# latdr31.net
KiCad netlist of a schematic drawn in EAGLE
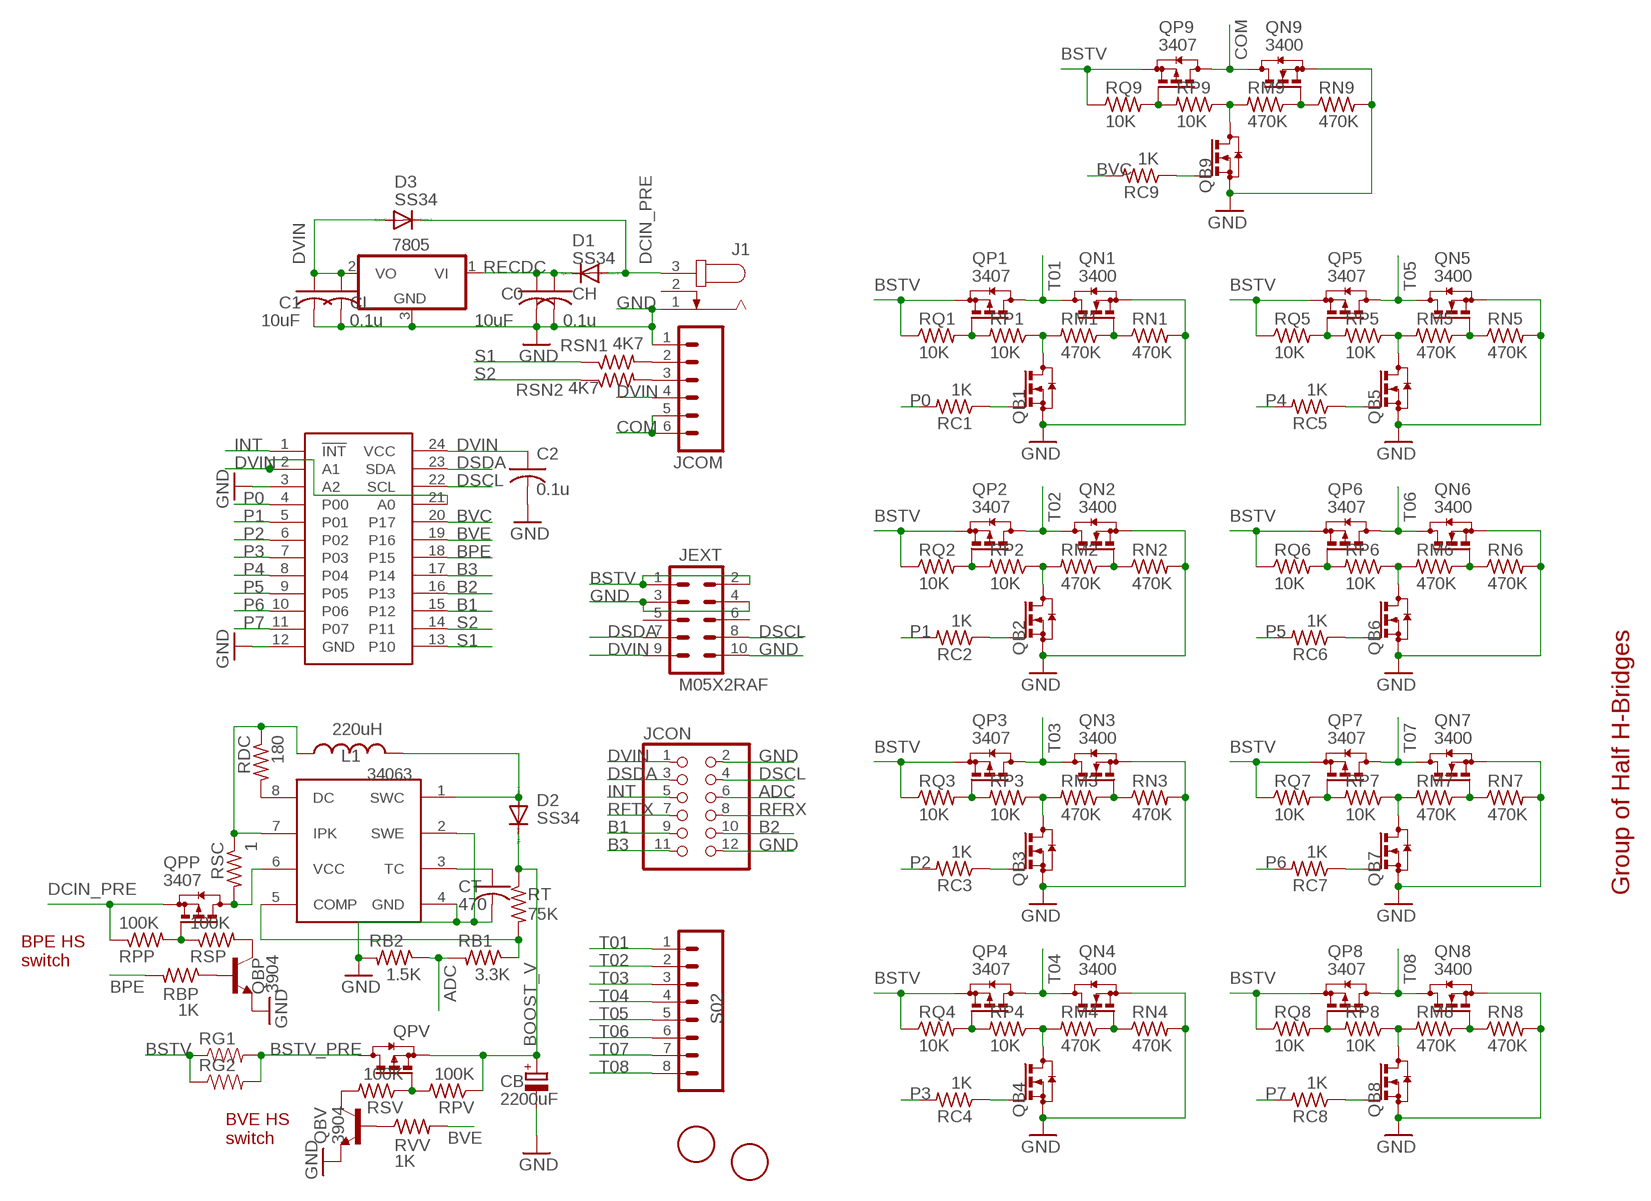
[diagram p0: schematic, sheet 1]

(export (version "E")
  (design (tool "Eeschema 10.0.6"))
  (components
    (comp (ref "0F")
      (value "FIDUCIAL")
      (footprint "eagle-import:FIDUCIAL_1MM")
      (libsource (lib "eagle-import") (part "FIDUCIAL"))
    )
    (comp (ref "1F")
      (value "FIDUCIAL")
      (footprint "eagle-import:FIDUCIAL_1MM")
      (libsource (lib "eagle-import") (part "FIDUCIAL"))
    )
    (comp (ref "7805")
      (value "7805DT")
      (footprint "eagle-import:TO252")
      (libsource (lib "eagle-import") (part "78DT05"))
    )
    (comp (ref "34063")
      (value "MC33063/MC34063D")
      (footprint "eagle-import:SO08")
      (libsource (lib "eagle-import") (part "MC33063/MC34063D"))
    )
    (comp (ref "C0")
      (value "10uF")
      (footprint "eagle-import:C0805K")
      (libsource (lib "eagle-import") (part "C-USC0805K"))
    )
    (comp (ref "C1")
      (value "10uF")
      (footprint "eagle-import:C0805K")
      (libsource (lib "eagle-import") (part "C-USC0805K"))
    )
    (comp (ref "C2")
      (value "0.1u")
      (footprint "eagle-import:C0603")
      (libsource (lib "eagle-import") (part "C-USC0603"))
    )
    (comp (ref "CB")
      (value "2200uF")
      (footprint "eagle-import:E7,5-16")
      (libsource (lib "eagle-import") (part "CPOL-EUE7.5-16"))
    )
    (comp (ref "CH")
      (value "0.1u")
      (footprint "eagle-import:C0603")
      (libsource (lib "eagle-import") (part "C-USC0603"))
    )
    (comp (ref "CL")
      (value "0.1u")
      (footprint "eagle-import:C0603")
      (libsource (lib "eagle-import") (part "C-USC0603"))
    )
    (comp (ref "CT")
      (value "470")
      (footprint "eagle-import:C0603K")
      (libsource (lib "eagle-import") (part "C-USC0603K"))
    )
    (comp (ref "D1")
      (value "SS34")
      (footprint "eagle-import:SMB")
      (libsource (lib "eagle-import") (part "DIODE-SMB"))
    )
    (comp (ref "D2")
      (value "SS34")
      (footprint "eagle-import:SMB")
      (libsource (lib "eagle-import") (part "DIODE-SMB"))
    )
    (comp (ref "D3")
      (value "SS34")
      (footprint "eagle-import:SMB")
      (libsource (lib "eagle-import") (part "DIODE-SMB"))
    )
    (comp (ref "J1")
      (value "JACK-PLUG0")
      (footprint "eagle-import:SPC4077")
      (libsource (lib "eagle-import") (part "JACK-PLUG0"))
    )
    (comp (ref "JCOM")
      (value "M065MM")
      (footprint "eagle-import:SCREWTERMINAL-5MM-6")
      (libsource (lib "eagle-import") (part "M065MM"))
    )
    (comp (ref "JCON")
      (value "PINHD-2X6")
      (footprint "eagle-import:2X06")
      (libsource (lib "eagle-import") (part "PINHD-2X6"))
    )
    (comp (ref "JEXT")
      (value "M05X2RAF")
      (footprint "eagle-import:2X5-RAF")
      (libsource (lib "eagle-import") (part "M05X2RAF"))
    )
    (comp (ref "L1")
      (value "220uH")
      (footprint "eagle-import:CR54")
      (libsource (lib "eagle-import") (part "INDUCTORCR54"))
    )
    (comp (ref "PCA9555")
      (value "PCF8575TSSOP24")
      (footprint "eagle-import:TSSOP24")
      (libsource (lib "eagle-import") (part "PCF8575TSSOP24"))
    )
    (comp (ref "QB1")
      (value "BSS123")
      (footprint "eagle-import:SOT23")
      (libsource (lib "eagle-import") (part "BSS123"))
    )
    (comp (ref "QB2")
      (value "BSS123")
      (footprint "eagle-import:SOT23")
      (libsource (lib "eagle-import") (part "BSS123"))
    )
    (comp (ref "QB3")
      (value "BSS123")
      (footprint "eagle-import:SOT23")
      (libsource (lib "eagle-import") (part "BSS123"))
    )
    (comp (ref "QB4")
      (value "BSS123")
      (footprint "eagle-import:SOT23")
      (libsource (lib "eagle-import") (part "BSS123"))
    )
    (comp (ref "QB5")
      (value "BSS123")
      (footprint "eagle-import:SOT23")
      (libsource (lib "eagle-import") (part "BSS123"))
    )
    (comp (ref "QB6")
      (value "BSS123")
      (footprint "eagle-import:SOT23")
      (libsource (lib "eagle-import") (part "BSS123"))
    )
    (comp (ref "QB7")
      (value "BSS123")
      (footprint "eagle-import:SOT23")
      (libsource (lib "eagle-import") (part "BSS123"))
    )
    (comp (ref "QB8")
      (value "BSS123")
      (footprint "eagle-import:SOT23")
      (libsource (lib "eagle-import") (part "BSS123"))
    )
    (comp (ref "QB9")
      (value "BSS123")
      (footprint "eagle-import:SOT23")
      (libsource (lib "eagle-import") (part "BSS123"))
    )
    (comp (ref "QBP")
      (value "3904")
      (footprint "eagle-import:SOT23-3")
      (libsource (lib "eagle-import") (part "TRANSISTOR_NPNSOT23-3"))
    )
    (comp (ref "QBV")
      (value "3904")
      (footprint "eagle-import:SOT23-3")
      (libsource (lib "eagle-import") (part "TRANSISTOR_NPNSOT23-3"))
    )
    (comp (ref "QN1")
      (value "3400")
      (footprint "eagle-import:SOT23")
      (libsource (lib "eagle-import") (part "BSS123"))
    )
    (comp (ref "QN2")
      (value "3400")
      (footprint "eagle-import:SOT23")
      (libsource (lib "eagle-import") (part "BSS123"))
    )
    (comp (ref "QN3")
      (value "3400")
      (footprint "eagle-import:SOT23")
      (libsource (lib "eagle-import") (part "BSS123"))
    )
    (comp (ref "QN4")
      (value "3400")
      (footprint "eagle-import:SOT23")
      (libsource (lib "eagle-import") (part "BSS123"))
    )
    (comp (ref "QN5")
      (value "3400")
      (footprint "eagle-import:SOT23")
      (libsource (lib "eagle-import") (part "BSS123"))
    )
    (comp (ref "QN6")
      (value "3400")
      (footprint "eagle-import:SOT23")
      (libsource (lib "eagle-import") (part "BSS123"))
    )
    (comp (ref "QN7")
      (value "3400")
      (footprint "eagle-import:SOT23")
      (libsource (lib "eagle-import") (part "BSS123"))
    )
    (comp (ref "QN8")
      (value "3400")
      (footprint "eagle-import:SOT23")
      (libsource (lib "eagle-import") (part "BSS123"))
    )
    (comp (ref "QN9")
      (value "3400")
      (footprint "eagle-import:SOT23")
      (libsource (lib "eagle-import") (part "BSS123"))
    )
    (comp (ref "QP1")
      (value "3407")
      (footprint "eagle-import:SOT23")
      (libsource (lib "eagle-import") (part "BSS84"))
    )
    (comp (ref "QP2")
      (value "3407")
      (footprint "eagle-import:SOT23")
      (libsource (lib "eagle-import") (part "BSS84"))
    )
    (comp (ref "QP3")
      (value "3407")
      (footprint "eagle-import:SOT23")
      (libsource (lib "eagle-import") (part "BSS84"))
    )
    (comp (ref "QP4")
      (value "3407")
      (footprint "eagle-import:SOT23")
      (libsource (lib "eagle-import") (part "BSS84"))
    )
    (comp (ref "QP5")
      (value "3407")
      (footprint "eagle-import:SOT23")
      (libsource (lib "eagle-import") (part "BSS84"))
    )
    (comp (ref "QP6")
      (value "3407")
      (footprint "eagle-import:SOT23")
      (libsource (lib "eagle-import") (part "BSS84"))
    )
    (comp (ref "QP7")
      (value "3407")
      (footprint "eagle-import:SOT23")
      (libsource (lib "eagle-import") (part "BSS84"))
    )
    (comp (ref "QP8")
      (value "3407")
      (footprint "eagle-import:SOT23")
      (libsource (lib "eagle-import") (part "BSS84"))
    )
    (comp (ref "QP9")
      (value "3407")
      (footprint "eagle-import:SOT23")
      (libsource (lib "eagle-import") (part "BSS84"))
    )
    (comp (ref "QPP")
      (value "3407")
      (footprint "eagle-import:SOT23")
      (libsource (lib "eagle-import") (part "BSS84"))
    )
    (comp (ref "QPV")
      (value "BSS84")
      (footprint "eagle-import:SOT23")
      (libsource (lib "eagle-import") (part "BSS84"))
    )
    (comp (ref "RB1")
      (value "3.3K")
      (footprint "eagle-import:R0603")
      (libsource (lib "eagle-import") (part "adafruitGood_R-US_R0603"))
    )
    (comp (ref "RB2")
      (value "1.5K")
      (footprint "eagle-import:R0603")
      (libsource (lib "eagle-import") (part "adafruitGood_R-US_R0603"))
    )
    (comp (ref "RBP")
      (value "1K")
      (footprint "eagle-import:R0603")
      (libsource (lib "eagle-import") (part "adafruitGood_R-US_R0603"))
    )
    (comp (ref "RC1")
      (value "1K")
      (footprint "eagle-import:R0603")
      (libsource (lib "eagle-import") (part "adafruitGood_R-US_R0603"))
    )
    (comp (ref "RC2")
      (value "1K")
      (footprint "eagle-import:R0603")
      (libsource (lib "eagle-import") (part "adafruitGood_R-US_R0603"))
    )
    (comp (ref "RC3")
      (value "1K")
      (footprint "eagle-import:R0603")
      (libsource (lib "eagle-import") (part "adafruitGood_R-US_R0603"))
    )
    (comp (ref "RC4")
      (value "1K")
      (footprint "eagle-import:R0603")
      (libsource (lib "eagle-import") (part "adafruitGood_R-US_R0603"))
    )
    (comp (ref "RC5")
      (value "1K")
      (footprint "eagle-import:R0603")
      (libsource (lib "eagle-import") (part "adafruitGood_R-US_R0603"))
    )
    (comp (ref "RC6")
      (value "1K")
      (footprint "eagle-import:R0603")
      (libsource (lib "eagle-import") (part "adafruitGood_R-US_R0603"))
    )
    (comp (ref "RC7")
      (value "1K")
      (footprint "eagle-import:R0603")
      (libsource (lib "eagle-import") (part "adafruitGood_R-US_R0603"))
    )
    (comp (ref "RC8")
      (value "1K")
      (footprint "eagle-import:R0603")
      (libsource (lib "eagle-import") (part "adafruitGood_R-US_R0603"))
    )
    (comp (ref "RC9")
      (value "1K")
      (footprint "eagle-import:R0603")
      (libsource (lib "eagle-import") (part "adafruitGood_R-US_R0603"))
    )
    (comp (ref "RDC")
      (value "180")
      (footprint "eagle-import:R0603")
      (libsource (lib "eagle-import") (part "adafruitGood_R-US_R0603"))
    )
    (comp (ref "RG1")
      (value "RESISTOR2512")
      (footprint "eagle-import:R2512")
      (libsource (lib "eagle-import") (part "RESISTOR2512"))
    )
    (comp (ref "RG2")
      (value "RESISTOR2512")
      (footprint "eagle-import:R2512")
      (libsource (lib "eagle-import") (part "RESISTOR2512"))
    )
    (comp (ref "RM1")
      (value "470K")
      (footprint "eagle-import:R0603")
      (libsource (lib "eagle-import") (part "adafruitGood_R-US_R0603"))
    )
    (comp (ref "RM2")
      (value "470K")
      (footprint "eagle-import:R0603")
      (libsource (lib "eagle-import") (part "adafruitGood_R-US_R0603"))
    )
    (comp (ref "RM3")
      (value "470K")
      (footprint "eagle-import:R0603")
      (libsource (lib "eagle-import") (part "adafruitGood_R-US_R0603"))
    )
    (comp (ref "RM4")
      (value "470K")
      (footprint "eagle-import:R0603")
      (libsource (lib "eagle-import") (part "adafruitGood_R-US_R0603"))
    )
    (comp (ref "RM5")
      (value "470K")
      (footprint "eagle-import:R0603")
      (libsource (lib "eagle-import") (part "adafruitGood_R-US_R0603"))
    )
    (comp (ref "RM6")
      (value "470K")
      (footprint "eagle-import:R0603")
      (libsource (lib "eagle-import") (part "adafruitGood_R-US_R0603"))
    )
    (comp (ref "RM7")
      (value "470K")
      (footprint "eagle-import:R0603")
      (libsource (lib "eagle-import") (part "adafruitGood_R-US_R0603"))
    )
    (comp (ref "RM8")
      (value "470K")
      (footprint "eagle-import:R0603")
      (libsource (lib "eagle-import") (part "adafruitGood_R-US_R0603"))
    )
    (comp (ref "RM9")
      (value "470K")
      (footprint "eagle-import:R0603")
      (libsource (lib "eagle-import") (part "adafruitGood_R-US_R0603"))
    )
    (comp (ref "RN1")
      (value "470K")
      (footprint "eagle-import:R0603")
      (libsource (lib "eagle-import") (part "adafruitGood_R-US_R0603"))
    )
    (comp (ref "RN2")
      (value "470K")
      (footprint "eagle-import:R0603")
      (libsource (lib "eagle-import") (part "adafruitGood_R-US_R0603"))
    )
    (comp (ref "RN3")
      (value "470K")
      (footprint "eagle-import:R0603")
      (libsource (lib "eagle-import") (part "adafruitGood_R-US_R0603"))
    )
    (comp (ref "RN4")
      (value "470K")
      (footprint "eagle-import:R0603")
      (libsource (lib "eagle-import") (part "adafruitGood_R-US_R0603"))
    )
    (comp (ref "RN5")
      (value "470K")
      (footprint "eagle-import:R0603")
      (libsource (lib "eagle-import") (part "adafruitGood_R-US_R0603"))
    )
    (comp (ref "RN6")
      (value "470K")
      (footprint "eagle-import:R0603")
      (libsource (lib "eagle-import") (part "adafruitGood_R-US_R0603"))
    )
    (comp (ref "RN7")
      (value "470K")
      (footprint "eagle-import:R0603")
      (libsource (lib "eagle-import") (part "adafruitGood_R-US_R0603"))
    )
    (comp (ref "RN8")
      (value "470K")
      (footprint "eagle-import:R0603")
      (libsource (lib "eagle-import") (part "adafruitGood_R-US_R0603"))
    )
    (comp (ref "RN9")
      (value "470K")
      (footprint "eagle-import:R0603")
      (libsource (lib "eagle-import") (part "adafruitGood_R-US_R0603"))
    )
    (comp (ref "RP1")
      (value "10K")
      (footprint "eagle-import:R0603")
      (libsource (lib "eagle-import") (part "adafruitGood_R-US_R0603"))
    )
    (comp (ref "RP2")
      (value "10K")
      (footprint "eagle-import:R0603")
      (libsource (lib "eagle-import") (part "adafruitGood_R-US_R0603"))
    )
    (comp (ref "RP3")
      (value "10K")
      (footprint "eagle-import:R0603")
      (libsource (lib "eagle-import") (part "adafruitGood_R-US_R0603"))
    )
    (comp (ref "RP4")
      (value "10K")
      (footprint "eagle-import:R0603")
      (libsource (lib "eagle-import") (part "adafruitGood_R-US_R0603"))
    )
    (comp (ref "RP5")
      (value "10K")
      (footprint "eagle-import:R0603")
      (libsource (lib "eagle-import") (part "adafruitGood_R-US_R0603"))
    )
    (comp (ref "RP6")
      (value "10K")
      (footprint "eagle-import:R0603")
      (libsource (lib "eagle-import") (part "adafruitGood_R-US_R0603"))
    )
    (comp (ref "RP7")
      (value "10K")
      (footprint "eagle-import:R0603")
      (libsource (lib "eagle-import") (part "adafruitGood_R-US_R0603"))
    )
    (comp (ref "RP8")
      (value "10K")
      (footprint "eagle-import:R0603")
      (libsource (lib "eagle-import") (part "adafruitGood_R-US_R0603"))
    )
    (comp (ref "RP9")
      (value "10K")
      (footprint "eagle-import:R0603")
      (libsource (lib "eagle-import") (part "adafruitGood_R-US_R0603"))
    )
    (comp (ref "RPP")
      (value "100K")
      (footprint "eagle-import:R0603")
      (libsource (lib "eagle-import") (part "adafruitGood_R-US_R0603"))
    )
    (comp (ref "RPV")
      (value "100K")
      (footprint "eagle-import:R0603")
      (libsource (lib "eagle-import") (part "adafruitGood_R-US_R0603"))
    )
    (comp (ref "RQ1")
      (value "10K")
      (footprint "eagle-import:R0603")
      (libsource (lib "eagle-import") (part "adafruitGood_R-US_R0603"))
    )
    (comp (ref "RQ2")
      (value "10K")
      (footprint "eagle-import:R0603")
      (libsource (lib "eagle-import") (part "adafruitGood_R-US_R0603"))
    )
    (comp (ref "RQ3")
      (value "10K")
      (footprint "eagle-import:R0603")
      (libsource (lib "eagle-import") (part "adafruitGood_R-US_R0603"))
    )
    (comp (ref "RQ4")
      (value "10K")
      (footprint "eagle-import:R0603")
      (libsource (lib "eagle-import") (part "adafruitGood_R-US_R0603"))
    )
    (comp (ref "RQ5")
      (value "10K")
      (footprint "eagle-import:R0603")
      (libsource (lib "eagle-import") (part "adafruitGood_R-US_R0603"))
    )
    (comp (ref "RQ6")
      (value "10K")
      (footprint "eagle-import:R0603")
      (libsource (lib "eagle-import") (part "adafruitGood_R-US_R0603"))
    )
    (comp (ref "RQ7")
      (value "10K")
      (footprint "eagle-import:R0603")
      (libsource (lib "eagle-import") (part "adafruitGood_R-US_R0603"))
    )
    (comp (ref "RQ8")
      (value "10K")
      (footprint "eagle-import:R0603")
      (libsource (lib "eagle-import") (part "adafruitGood_R-US_R0603"))
    )
    (comp (ref "RQ9")
      (value "10K")
      (footprint "eagle-import:R0603")
      (libsource (lib "eagle-import") (part "adafruitGood_R-US_R0603"))
    )
    (comp (ref "RSC")
      (value "1")
      (footprint "eagle-import:R0603")
      (libsource (lib "eagle-import") (part "adafruitGood_R-US_R0603"))
    )
    (comp (ref "RSN1")
      (value "4K7")
      (footprint "eagle-import:R0603")
      (libsource (lib "eagle-import") (part "R-US_R0603"))
    )
    (comp (ref "RSN2")
      (value "4K7")
      (footprint "eagle-import:R0603")
      (libsource (lib "eagle-import") (part "R-US_R0603"))
    )
    (comp (ref "RSP")
      (value "100K")
      (footprint "eagle-import:R0603")
      (libsource (lib "eagle-import") (part "adafruitGood_R-US_R0603"))
    )
    (comp (ref "RSV")
      (value "100K")
      (footprint "eagle-import:R0603")
      (libsource (lib "eagle-import") (part "adafruitGood_R-US_R0603"))
    )
    (comp (ref "RT")
      (value "75K")
      (footprint "eagle-import:R0603")
      (libsource (lib "eagle-import") (part "adafruitGood_R-US_R0603"))
    )
    (comp (ref "RVV")
      (value "1K")
      (footprint "eagle-import:R0603")
      (libsource (lib "eagle-import") (part "adafruitGood_R-US_R0603"))
    )
    (comp (ref "S02")
      (value "M085MM-8")
      (footprint "eagle-import:SCREWTERMINAL-5MM-8")
      (libsource (lib "eagle-import") (part "M085MM-8"))
    )
  )
  (nets
    (net (code "1") (name "/ADC") (class "Default")
      (node (ref "JCON") (pin "6") (pinfunction "6_6") (pintype "passive"))
      (node (ref "RB1") (pin "2") (pinfunction "2_2") (pintype "passive"))
      (node (ref "RB2") (pin "1") (pinfunction "1_1") (pintype "passive"))
    )
    (net (code "2") (name "/B1") (class "Default")
      (node (ref "JCON") (pin "9") (pinfunction "9_9") (pintype "passive"))
      (node (ref "PCA9555") (pin "15") (pinfunction "P12_15") (pintype "bidirectional"))
    )
    (net (code "3") (name "/B2") (class "Default")
      (node (ref "JCON") (pin "10") (pinfunction "10_10") (pintype "passive"))
      (node (ref "PCA9555") (pin "16") (pinfunction "P13_16") (pintype "bidirectional"))
    )
    (net (code "4") (name "/B3") (class "Default")
      (node (ref "JCON") (pin "11") (pinfunction "11_11") (pintype "passive"))
      (node (ref "PCA9555") (pin "17") (pinfunction "P14_17") (pintype "bidirectional"))
    )
    (net (code "5") (name "/BOOST_V") (class "Default")
      (node (ref "CB") (pin "+") (pinfunction "+_+") (pintype "passive"))
      (node (ref "D2") (pin "C") (pinfunction "C_C") (pintype "passive"))
      (node (ref "QPV") (pin "2") (pinfunction "S_2") (pintype "passive"))
      (node (ref "RPV") (pin "1") (pinfunction "1_1") (pintype "passive"))
      (node (ref "RT") (pin "1") (pinfunction "1_1") (pintype "passive"))
    )
    (net (code "6") (name "/BPE") (class "Default")
      (node (ref "PCA9555") (pin "18") (pinfunction "P15_18") (pintype "bidirectional"))
      (node (ref "RBP") (pin "2") (pinfunction "2_2") (pintype "passive"))
    )
    (net (code "7") (name "/BSTV") (class "Default")
      (node (ref "JEXT") (pin "1") (pinfunction "1_1") (pintype "passive"))
      (node (ref "JEXT") (pin "2") (pinfunction "2_2") (pintype "passive"))
      (node (ref "QP1") (pin "2") (pinfunction "S_2") (pintype "passive"))
      (node (ref "QP2") (pin "2") (pinfunction "S_2") (pintype "passive"))
      (node (ref "QP3") (pin "2") (pinfunction "S_2") (pintype "passive"))
      (node (ref "QP4") (pin "2") (pinfunction "S_2") (pintype "passive"))
      (node (ref "QP5") (pin "2") (pinfunction "S_2") (pintype "passive"))
      (node (ref "QP6") (pin "2") (pinfunction "S_2") (pintype "passive"))
      (node (ref "QP7") (pin "2") (pinfunction "S_2") (pintype "passive"))
      (node (ref "QP8") (pin "2") (pinfunction "S_2") (pintype "passive"))
      (node (ref "QP9") (pin "2") (pinfunction "S_2") (pintype "passive"))
      (node (ref "RG1") (pin "1") (pinfunction "1_1") (pintype "passive"))
      (node (ref "RG2") (pin "1") (pinfunction "1_1") (pintype "passive"))
      (node (ref "RQ1") (pin "1") (pinfunction "1_1") (pintype "passive"))
      (node (ref "RQ2") (pin "1") (pinfunction "1_1") (pintype "passive"))
      (node (ref "RQ3") (pin "1") (pinfunction "1_1") (pintype "passive"))
      (node (ref "RQ4") (pin "1") (pinfunction "1_1") (pintype "passive"))
      (node (ref "RQ5") (pin "1") (pinfunction "1_1") (pintype "passive"))
      (node (ref "RQ6") (pin "1") (pinfunction "1_1") (pintype "passive"))
      (node (ref "RQ7") (pin "1") (pinfunction "1_1") (pintype "passive"))
      (node (ref "RQ8") (pin "1") (pinfunction "1_1") (pintype "passive"))
      (node (ref "RQ9") (pin "1") (pinfunction "1_1") (pintype "passive"))
    )
    (net (code "8") (name "/BSTV_PRE") (class "Default")
      (node (ref "QPV") (pin "3") (pinfunction "D_3") (pintype "passive"))
      (node (ref "RG1") (pin "2") (pinfunction "2_2") (pintype "passive"))
      (node (ref "RG2") (pin "2") (pinfunction "2_2") (pintype "passive"))
    )
    (net (code "9") (name "/BVC") (class "Default")
      (node (ref "PCA9555") (pin "20") (pinfunction "P17_20") (pintype "bidirectional"))
      (node (ref "RC9") (pin "2") (pinfunction "2_2") (pintype "passive"))
    )
    (net (code "10") (name "/BVE") (class "Default")
      (node (ref "PCA9555") (pin "19") (pinfunction "P16_19") (pintype "bidirectional"))
      (node (ref "RVV") (pin "2") (pinfunction "2_2") (pintype "passive"))
    )
    (net (code "11") (name "/COM") (class "Default")
      (node (ref "JCOM") (pin "5") (pinfunction "5_5") (pintype "passive"))
      (node (ref "JCOM") (pin "6") (pinfunction "6_6") (pintype "passive"))
      (node (ref "QN9") (pin "3") (pinfunction "D_3") (pintype "passive"))
      (node (ref "QP9") (pin "3") (pinfunction "D_3") (pintype "passive"))
    )
    (net (code "12") (name "/DCIN_PRE") (class "Default")
      (node (ref "D1") (pin "A") (pinfunction "A_A") (pintype "passive"))
      (node (ref "D3") (pin "C") (pinfunction "C_C") (pintype "passive"))
      (node (ref "J1") (pin "3") (pinfunction "3_3") (pintype "passive"))
      (node (ref "QPP") (pin "2") (pinfunction "S_2") (pintype "passive"))
      (node (ref "RPP") (pin "1") (pinfunction "1_1") (pintype "passive"))
    )
    (net (code "13") (name "/DSCL") (class "Default")
      (node (ref "JCON") (pin "4") (pinfunction "4_4") (pintype "passive"))
      (node (ref "JEXT") (pin "8") (pinfunction "8_8") (pintype "passive"))
      (node (ref "PCA9555") (pin "22") (pinfunction "SCL_22") (pintype "bidirectional"))
    )
    (net (code "14") (name "/DSDA") (class "Default")
      (node (ref "JCON") (pin "3") (pinfunction "3_3") (pintype "passive"))
      (node (ref "JEXT") (pin "7") (pinfunction "7_7") (pintype "passive"))
      (node (ref "PCA9555") (pin "23") (pinfunction "SDA_23") (pintype "bidirectional"))
    )
    (net (code "15") (name "/DVIN") (class "Default")
      (node (ref "7805") (pin "2") (pinfunction "VO_2") (pintype "passive"))
      (node (ref "C1") (pin "1") (pinfunction "1_1") (pintype "passive"))
      (node (ref "C2") (pin "1") (pinfunction "1_1") (pintype "passive"))
      (node (ref "CL") (pin "1") (pinfunction "1_1") (pintype "passive"))
      (node (ref "D3") (pin "A") (pinfunction "A_A") (pintype "passive"))
      (node (ref "JCOM") (pin "4") (pinfunction "4_4") (pintype "passive"))
      (node (ref "JCON") (pin "1") (pinfunction "1_1") (pintype "passive"))
      (node (ref "JEXT") (pin "9") (pinfunction "9_9") (pintype "passive"))
      (node (ref "PCA9555") (pin "2") (pinfunction "A1_2") (pintype "bidirectional"))
      (node (ref "PCA9555") (pin "21") (pinfunction "A0_21") (pintype "bidirectional"))
      (node (ref "PCA9555") (pin "24") (pinfunction "VCC_24") (pintype "power_in"))
    )
    (net (code "16") (name "/INT") (class "Default")
      (node (ref "JCON") (pin "5") (pinfunction "5_5") (pintype "passive"))
      (node (ref "PCA9555") (pin "1") (pinfunction "~{INT}_1") (pintype "bidirectional"))
    )
    (net (code "17") (name "/P0") (class "Default")
      (node (ref "PCA9555") (pin "4") (pinfunction "P00_4") (pintype "bidirectional"))
      (node (ref "RC1") (pin "2") (pinfunction "2_2") (pintype "passive"))
    )
    (net (code "18") (name "/P1") (class "Default")
      (node (ref "PCA9555") (pin "5") (pinfunction "P01_5") (pintype "bidirectional"))
      (node (ref "RC2") (pin "2") (pinfunction "2_2") (pintype "passive"))
    )
    (net (code "19") (name "/P2") (class "Default")
      (node (ref "PCA9555") (pin "6") (pinfunction "P02_6") (pintype "bidirectional"))
      (node (ref "RC3") (pin "2") (pinfunction "2_2") (pintype "passive"))
    )
    (net (code "20") (name "/P3") (class "Default")
      (node (ref "PCA9555") (pin "7") (pinfunction "P03_7") (pintype "bidirectional"))
      (node (ref "RC4") (pin "2") (pinfunction "2_2") (pintype "passive"))
    )
    (net (code "21") (name "/P4") (class "Default")
      (node (ref "PCA9555") (pin "8") (pinfunction "P04_8") (pintype "bidirectional"))
      (node (ref "RC5") (pin "2") (pinfunction "2_2") (pintype "passive"))
    )
    (net (code "22") (name "/P5") (class "Default")
      (node (ref "PCA9555") (pin "9") (pinfunction "P05_9") (pintype "bidirectional"))
      (node (ref "RC6") (pin "2") (pinfunction "2_2") (pintype "passive"))
    )
    (net (code "23") (name "/P6") (class "Default")
      (node (ref "PCA9555") (pin "10") (pinfunction "P06_10") (pintype "bidirectional"))
      (node (ref "RC7") (pin "2") (pinfunction "2_2") (pintype "passive"))
    )
    (net (code "24") (name "/P7") (class "Default")
      (node (ref "PCA9555") (pin "11") (pinfunction "P07_11") (pintype "bidirectional"))
      (node (ref "RC8") (pin "2") (pinfunction "2_2") (pintype "passive"))
    )
    (net (code "25") (name "/RECDC") (class "Default")
      (node (ref "7805") (pin "1") (pinfunction "VI_1") (pintype "input"))
      (node (ref "C0") (pin "1") (pinfunction "1_1") (pintype "passive"))
      (node (ref "CH") (pin "1") (pinfunction "1_1") (pintype "passive"))
      (node (ref "D1") (pin "C") (pinfunction "C_C") (pintype "passive"))
    )
    (net (code "26") (name "/RFRX") (class "Default")
      (node (ref "JCON") (pin "8") (pinfunction "8_8") (pintype "passive"))
    )
    (net (code "27") (name "/RFTX") (class "Default")
      (node (ref "JCON") (pin "7") (pinfunction "7_7") (pintype "passive"))
    )
    (net (code "28") (name "/S1") (class "Default")
      (node (ref "PCA9555") (pin "13") (pinfunction "P10_13") (pintype "bidirectional"))
      (node (ref "RSN1") (pin "1") (pinfunction "1_1") (pintype "passive"))
    )
    (net (code "29") (name "/S2") (class "Default")
      (node (ref "PCA9555") (pin "14") (pinfunction "P11_14") (pintype "bidirectional"))
      (node (ref "RSN2") (pin "1") (pinfunction "1_1") (pintype "passive"))
    )
    (net (code "30") (name "/T01") (class "Default")
      (node (ref "QN1") (pin "3") (pinfunction "D_3") (pintype "passive"))
      (node (ref "QP1") (pin "3") (pinfunction "D_3") (pintype "passive"))
      (node (ref "S02") (pin "1") (pinfunction "1_1") (pintype "passive"))
    )
    (net (code "31") (name "/T02") (class "Default")
      (node (ref "QN2") (pin "3") (pinfunction "D_3") (pintype "passive"))
      (node (ref "QP2") (pin "3") (pinfunction "D_3") (pintype "passive"))
      (node (ref "S02") (pin "2") (pinfunction "2_2") (pintype "passive"))
    )
    (net (code "32") (name "/T03") (class "Default")
      (node (ref "QN3") (pin "3") (pinfunction "D_3") (pintype "passive"))
      (node (ref "QP3") (pin "3") (pinfunction "D_3") (pintype "passive"))
      (node (ref "S02") (pin "3") (pinfunction "3_3") (pintype "passive"))
    )
    (net (code "33") (name "/T04") (class "Default")
      (node (ref "QN4") (pin "3") (pinfunction "D_3") (pintype "passive"))
      (node (ref "QP4") (pin "3") (pinfunction "D_3") (pintype "passive"))
      (node (ref "S02") (pin "4") (pinfunction "4_4") (pintype "passive"))
    )
    (net (code "34") (name "/T05") (class "Default")
      (node (ref "QN5") (pin "3") (pinfunction "D_3") (pintype "passive"))
      (node (ref "QP5") (pin "3") (pinfunction "D_3") (pintype "passive"))
      (node (ref "S02") (pin "5") (pinfunction "5_5") (pintype "passive"))
    )
    (net (code "35") (name "/T06") (class "Default")
      (node (ref "QN6") (pin "3") (pinfunction "D_3") (pintype "passive"))
      (node (ref "QP6") (pin "3") (pinfunction "D_3") (pintype "passive"))
      (node (ref "S02") (pin "6") (pinfunction "6_6") (pintype "passive"))
    )
    (net (code "36") (name "/T07") (class "Default")
      (node (ref "QN7") (pin "3") (pinfunction "D_3") (pintype "passive"))
      (node (ref "QP7") (pin "3") (pinfunction "D_3") (pintype "passive"))
      (node (ref "S02") (pin "7") (pinfunction "7_7") (pintype "passive"))
    )
    (net (code "37") (name "/T08") (class "Default")
      (node (ref "QN8") (pin "3") (pinfunction "D_3") (pintype "passive"))
      (node (ref "QP8") (pin "3") (pinfunction "D_3") (pintype "passive"))
      (node (ref "S02") (pin "8") (pinfunction "8_8") (pintype "passive"))
    )
    (net (code "38") (name "GND") (class "Default")
      (node (ref "34063") (pin "2") (pinfunction "SWE_2") (pintype "input"))
      (node (ref "34063") (pin "4") (pinfunction "GND_4") (pintype "power_in"))
      (node (ref "7805") (pin "3") (pinfunction "GND_3") (pintype "passive"))
      (node (ref "C0") (pin "2") (pinfunction "2_2") (pintype "passive"))
      (node (ref "C1") (pin "2") (pinfunction "2_2") (pintype "passive"))
      (node (ref "C2") (pin "2") (pinfunction "2_2") (pintype "passive"))
      (node (ref "CB") (pin "-") (pinfunction "-_-") (pintype "passive"))
      (node (ref "CH") (pin "2") (pinfunction "2_2") (pintype "passive"))
      (node (ref "CL") (pin "2") (pinfunction "2_2") (pintype "passive"))
      (node (ref "CT") (pin "2") (pinfunction "2_2") (pintype "passive"))
      (node (ref "J1") (pin "1") (pinfunction "1_1") (pintype "passive"))
      (node (ref "JCOM") (pin "1") (pinfunction "1_1") (pintype "passive"))
      (node (ref "JCON") (pin "12") (pinfunction "12_12") (pintype "passive"))
      (node (ref "JCON") (pin "2") (pinfunction "2_2") (pintype "passive"))
      (node (ref "JEXT") (pin "10") (pinfunction "10_10") (pintype "passive"))
      (node (ref "JEXT") (pin "3") (pinfunction "3_3") (pintype "passive"))
      (node (ref "JEXT") (pin "4") (pinfunction "4_4") (pintype "passive"))
      (node (ref "PCA9555") (pin "12") (pinfunction "GND_12") (pintype "power_in"))
      (node (ref "PCA9555") (pin "3") (pinfunction "A2_3") (pintype "bidirectional"))
      (node (ref "QB1") (pin "2") (pinfunction "S_2") (pintype "passive"))
      (node (ref "QB2") (pin "2") (pinfunction "S_2") (pintype "passive"))
      (node (ref "QB3") (pin "2") (pinfunction "S_2") (pintype "passive"))
      (node (ref "QB4") (pin "2") (pinfunction "S_2") (pintype "passive"))
      (node (ref "QB5") (pin "2") (pinfunction "S_2") (pintype "passive"))
      (node (ref "QB6") (pin "2") (pinfunction "S_2") (pintype "passive"))
      (node (ref "QB7") (pin "2") (pinfunction "S_2") (pintype "passive"))
      (node (ref "QB8") (pin "2") (pinfunction "S_2") (pintype "passive"))
      (node (ref "QB9") (pin "2") (pinfunction "S_2") (pintype "passive"))
      (node (ref "QBP") (pin "2") (pinfunction "E_2") (pintype "passive"))
      (node (ref "QBV") (pin "2") (pinfunction "E_2") (pintype "passive"))
      (node (ref "QN1") (pin "2") (pinfunction "S_2") (pintype "passive"))
      (node (ref "QN2") (pin "2") (pinfunction "S_2") (pintype "passive"))
      (node (ref "QN3") (pin "2") (pinfunction "S_2") (pintype "passive"))
      (node (ref "QN4") (pin "2") (pinfunction "S_2") (pintype "passive"))
      (node (ref "QN5") (pin "2") (pinfunction "S_2") (pintype "passive"))
      (node (ref "QN6") (pin "2") (pinfunction "S_2") (pintype "passive"))
      (node (ref "QN7") (pin "2") (pinfunction "S_2") (pintype "passive"))
      (node (ref "QN8") (pin "2") (pinfunction "S_2") (pintype "passive"))
      (node (ref "QN9") (pin "2") (pinfunction "S_2") (pintype "passive"))
      (node (ref "RB2") (pin "2") (pinfunction "2_2") (pintype "passive"))
      (node (ref "RN1") (pin "2") (pinfunction "2_2") (pintype "passive"))
      (node (ref "RN2") (pin "2") (pinfunction "2_2") (pintype "passive"))
      (node (ref "RN3") (pin "2") (pinfunction "2_2") (pintype "passive"))
      (node (ref "RN4") (pin "2") (pinfunction "2_2") (pintype "passive"))
      (node (ref "RN5") (pin "2") (pinfunction "2_2") (pintype "passive"))
      (node (ref "RN6") (pin "2") (pinfunction "2_2") (pintype "passive"))
      (node (ref "RN7") (pin "2") (pinfunction "2_2") (pintype "passive"))
      (node (ref "RN8") (pin "2") (pinfunction "2_2") (pintype "passive"))
      (node (ref "RN9") (pin "2") (pinfunction "2_2") (pintype "passive"))
    )
    (net (code "39") (name "Net-(34063-COMP)") (class "Default")
      (node (ref "34063") (pin "5") (pinfunction "COMP_5") (pintype "input"))
      (node (ref "RB1") (pin "1") (pinfunction "1_1") (pintype "passive"))
      (node (ref "RT") (pin "2") (pinfunction "2_2") (pintype "passive"))
    )
    (net (code "40") (name "Net-(34063-DC)") (class "Default")
      (node (ref "34063") (pin "8") (pinfunction "DC_8") (pintype "input"))
      (node (ref "RDC") (pin "2") (pinfunction "2_2") (pintype "passive"))
    )
    (net (code "41") (name "Net-(34063-IPK)") (class "Default")
      (node (ref "34063") (pin "7") (pinfunction "IPK_7") (pintype "bidirectional"))
      (node (ref "L1") (pin "P$1") (pinfunction "1_P$1") (pintype "passive"))
      (node (ref "RDC") (pin "1") (pinfunction "1_1") (pintype "passive"))
      (node (ref "RSC") (pin "1") (pinfunction "1_1") (pintype "passive"))
    )
    (net (code "42") (name "Net-(34063-SWC)") (class "Default")
      (node (ref "34063") (pin "1") (pinfunction "SWC_1") (pintype "input"))
      (node (ref "D2") (pin "A") (pinfunction "A_A") (pintype "passive"))
      (node (ref "L1") (pin "P$2") (pinfunction "2_P$2") (pintype "passive"))
    )
    (net (code "43") (name "Net-(34063-TC)") (class "Default")
      (node (ref "34063") (pin "3") (pinfunction "TC_3") (pintype "input"))
      (node (ref "CT") (pin "1") (pinfunction "1_1") (pintype "passive"))
    )
    (net (code "44") (name "Net-(34063-VCC)") (class "Default")
      (node (ref "34063") (pin "6") (pinfunction "VCC_6") (pintype "power_in"))
      (node (ref "QPP") (pin "3") (pinfunction "D_3") (pintype "passive"))
      (node (ref "RSC") (pin "2") (pinfunction "2_2") (pintype "passive"))
    )
    (net (code "45") (name "Net-(JCOM-Pad2)") (class "Default")
      (node (ref "JCOM") (pin "2") (pinfunction "2_2") (pintype "passive"))
      (node (ref "RSN1") (pin "2") (pinfunction "2_2") (pintype "passive"))
    )
    (net (code "46") (name "Net-(JCOM-Pad3)") (class "Default")
      (node (ref "JCOM") (pin "3") (pinfunction "3_3") (pintype "passive"))
      (node (ref "RSN2") (pin "2") (pinfunction "2_2") (pintype "passive"))
    )
    (net (code "47") (name "Net-(QB1-D)") (class "Default")
      (node (ref "QB1") (pin "3") (pinfunction "D_3") (pintype "passive"))
      (node (ref "RM1") (pin "2") (pinfunction "2_2") (pintype "passive"))
      (node (ref "RP1") (pin "1") (pinfunction "1_1") (pintype "passive"))
    )
    (net (code "48") (name "Net-(QB1-G)") (class "Default")
      (node (ref "QB1") (pin "1") (pinfunction "G_1") (pintype "passive"))
      (node (ref "RC1") (pin "1") (pinfunction "1_1") (pintype "passive"))
    )
    (net (code "49") (name "Net-(QB2-D)") (class "Default")
      (node (ref "QB2") (pin "3") (pinfunction "D_3") (pintype "passive"))
      (node (ref "RM2") (pin "2") (pinfunction "2_2") (pintype "passive"))
      (node (ref "RP2") (pin "1") (pinfunction "1_1") (pintype "passive"))
    )
    (net (code "50") (name "Net-(QB2-G)") (class "Default")
      (node (ref "QB2") (pin "1") (pinfunction "G_1") (pintype "passive"))
      (node (ref "RC2") (pin "1") (pinfunction "1_1") (pintype "passive"))
    )
    (net (code "51") (name "Net-(QB3-D)") (class "Default")
      (node (ref "QB3") (pin "3") (pinfunction "D_3") (pintype "passive"))
      (node (ref "RM3") (pin "2") (pinfunction "2_2") (pintype "passive"))
      (node (ref "RP3") (pin "1") (pinfunction "1_1") (pintype "passive"))
    )
    (net (code "52") (name "Net-(QB3-G)") (class "Default")
      (node (ref "QB3") (pin "1") (pinfunction "G_1") (pintype "passive"))
      (node (ref "RC3") (pin "1") (pinfunction "1_1") (pintype "passive"))
    )
    (net (code "53") (name "Net-(QB4-D)") (class "Default")
      (node (ref "QB4") (pin "3") (pinfunction "D_3") (pintype "passive"))
      (node (ref "RM4") (pin "2") (pinfunction "2_2") (pintype "passive"))
      (node (ref "RP4") (pin "1") (pinfunction "1_1") (pintype "passive"))
    )
    (net (code "54") (name "Net-(QB4-G)") (class "Default")
      (node (ref "QB4") (pin "1") (pinfunction "G_1") (pintype "passive"))
      (node (ref "RC4") (pin "1") (pinfunction "1_1") (pintype "passive"))
    )
    (net (code "55") (name "Net-(QB5-D)") (class "Default")
      (node (ref "QB5") (pin "3") (pinfunction "D_3") (pintype "passive"))
      (node (ref "RM5") (pin "2") (pinfunction "2_2") (pintype "passive"))
      (node (ref "RP5") (pin "1") (pinfunction "1_1") (pintype "passive"))
    )
    (net (code "56") (name "Net-(QB5-G)") (class "Default")
      (node (ref "QB5") (pin "1") (pinfunction "G_1") (pintype "passive"))
      (node (ref "RC5") (pin "1") (pinfunction "1_1") (pintype "passive"))
    )
    (net (code "57") (name "Net-(QB6-D)") (class "Default")
      (node (ref "QB6") (pin "3") (pinfunction "D_3") (pintype "passive"))
      (node (ref "RM6") (pin "2") (pinfunction "2_2") (pintype "passive"))
      (node (ref "RP6") (pin "1") (pinfunction "1_1") (pintype "passive"))
    )
    (net (code "58") (name "Net-(QB6-G)") (class "Default")
      (node (ref "QB6") (pin "1") (pinfunction "G_1") (pintype "passive"))
      (node (ref "RC6") (pin "1") (pinfunction "1_1") (pintype "passive"))
    )
    (net (code "59") (name "Net-(QB7-D)") (class "Default")
      (node (ref "QB7") (pin "3") (pinfunction "D_3") (pintype "passive"))
      (node (ref "RM7") (pin "2") (pinfunction "2_2") (pintype "passive"))
      (node (ref "RP7") (pin "1") (pinfunction "1_1") (pintype "passive"))
    )
    (net (code "60") (name "Net-(QB7-G)") (class "Default")
      (node (ref "QB7") (pin "1") (pinfunction "G_1") (pintype "passive"))
      (node (ref "RC7") (pin "1") (pinfunction "1_1") (pintype "passive"))
    )
    (net (code "61") (name "Net-(QB8-D)") (class "Default")
      (node (ref "QB8") (pin "3") (pinfunction "D_3") (pintype "passive"))
      (node (ref "RM8") (pin "2") (pinfunction "2_2") (pintype "passive"))
      (node (ref "RP8") (pin "1") (pinfunction "1_1") (pintype "passive"))
    )
    (net (code "62") (name "Net-(QB8-G)") (class "Default")
      (node (ref "QB8") (pin "1") (pinfunction "G_1") (pintype "passive"))
      (node (ref "RC8") (pin "1") (pinfunction "1_1") (pintype "passive"))
    )
    (net (code "63") (name "Net-(QB9-D)") (class "Default")
      (node (ref "QB9") (pin "3") (pinfunction "D_3") (pintype "passive"))
      (node (ref "RM9") (pin "2") (pinfunction "2_2") (pintype "passive"))
      (node (ref "RP9") (pin "1") (pinfunction "1_1") (pintype "passive"))
    )
    (net (code "64") (name "Net-(QB9-G)") (class "Default")
      (node (ref "QB9") (pin "1") (pinfunction "G_1") (pintype "passive"))
      (node (ref "RC9") (pin "1") (pinfunction "1_1") (pintype "passive"))
    )
    (net (code "65") (name "Net-(QBP-B)") (class "Default")
      (node (ref "QBP") (pin "1") (pinfunction "B_1") (pintype "passive"))
      (node (ref "RBP") (pin "1") (pinfunction "1_1") (pintype "passive"))
    )
    (net (code "66") (name "Net-(QBP-C)") (class "Default")
      (node (ref "QBP") (pin "3") (pinfunction "C_3") (pintype "passive"))
      (node (ref "RSP") (pin "2") (pinfunction "2_2") (pintype "passive"))
    )
    (net (code "67") (name "Net-(QBV-B)") (class "Default")
      (node (ref "QBV") (pin "1") (pinfunction "B_1") (pintype "passive"))
      (node (ref "RVV") (pin "1") (pinfunction "1_1") (pintype "passive"))
    )
    (net (code "68") (name "Net-(QBV-C)") (class "Default")
      (node (ref "QBV") (pin "3") (pinfunction "C_3") (pintype "passive"))
      (node (ref "RSV") (pin "2") (pinfunction "2_2") (pintype "passive"))
    )
    (net (code "69") (name "Net-(QN1-G)") (class "Default")
      (node (ref "QN1") (pin "1") (pinfunction "G_1") (pintype "passive"))
      (node (ref "RM1") (pin "1") (pinfunction "1_1") (pintype "passive"))
      (node (ref "RN1") (pin "1") (pinfunction "1_1") (pintype "passive"))
    )
    (net (code "70") (name "Net-(QN2-G)") (class "Default")
      (node (ref "QN2") (pin "1") (pinfunction "G_1") (pintype "passive"))
      (node (ref "RM2") (pin "1") (pinfunction "1_1") (pintype "passive"))
      (node (ref "RN2") (pin "1") (pinfunction "1_1") (pintype "passive"))
    )
    (net (code "71") (name "Net-(QN3-G)") (class "Default")
      (node (ref "QN3") (pin "1") (pinfunction "G_1") (pintype "passive"))
      (node (ref "RM3") (pin "1") (pinfunction "1_1") (pintype "passive"))
      (node (ref "RN3") (pin "1") (pinfunction "1_1") (pintype "passive"))
    )
    (net (code "72") (name "Net-(QN4-G)") (class "Default")
      (node (ref "QN4") (pin "1") (pinfunction "G_1") (pintype "passive"))
      (node (ref "RM4") (pin "1") (pinfunction "1_1") (pintype "passive"))
      (node (ref "RN4") (pin "1") (pinfunction "1_1") (pintype "passive"))
    )
    (net (code "73") (name "Net-(QN5-G)") (class "Default")
      (node (ref "QN5") (pin "1") (pinfunction "G_1") (pintype "passive"))
      (node (ref "RM5") (pin "1") (pinfunction "1_1") (pintype "passive"))
      (node (ref "RN5") (pin "1") (pinfunction "1_1") (pintype "passive"))
    )
    (net (code "74") (name "Net-(QN6-G)") (class "Default")
      (node (ref "QN6") (pin "1") (pinfunction "G_1") (pintype "passive"))
      (node (ref "RM6") (pin "1") (pinfunction "1_1") (pintype "passive"))
      (node (ref "RN6") (pin "1") (pinfunction "1_1") (pintype "passive"))
    )
    (net (code "75") (name "Net-(QN7-G)") (class "Default")
      (node (ref "QN7") (pin "1") (pinfunction "G_1") (pintype "passive"))
      (node (ref "RM7") (pin "1") (pinfunction "1_1") (pintype "passive"))
      (node (ref "RN7") (pin "1") (pinfunction "1_1") (pintype "passive"))
    )
    (net (code "76") (name "Net-(QN8-G)") (class "Default")
      (node (ref "QN8") (pin "1") (pinfunction "G_1") (pintype "passive"))
      (node (ref "RM8") (pin "1") (pinfunction "1_1") (pintype "passive"))
      (node (ref "RN8") (pin "1") (pinfunction "1_1") (pintype "passive"))
    )
    (net (code "77") (name "Net-(QN9-G)") (class "Default")
      (node (ref "QN9") (pin "1") (pinfunction "G_1") (pintype "passive"))
      (node (ref "RM9") (pin "1") (pinfunction "1_1") (pintype "passive"))
      (node (ref "RN9") (pin "1") (pinfunction "1_1") (pintype "passive"))
    )
    (net (code "78") (name "Net-(QP1-G)") (class "Default")
      (node (ref "QP1") (pin "1") (pinfunction "G_1") (pintype "passive"))
      (node (ref "RP1") (pin "2") (pinfunction "2_2") (pintype "passive"))
      (node (ref "RQ1") (pin "2") (pinfunction "2_2") (pintype "passive"))
    )
    (net (code "79") (name "Net-(QP2-G)") (class "Default")
      (node (ref "QP2") (pin "1") (pinfunction "G_1") (pintype "passive"))
      (node (ref "RP2") (pin "2") (pinfunction "2_2") (pintype "passive"))
      (node (ref "RQ2") (pin "2") (pinfunction "2_2") (pintype "passive"))
    )
    (net (code "80") (name "Net-(QP3-G)") (class "Default")
      (node (ref "QP3") (pin "1") (pinfunction "G_1") (pintype "passive"))
      (node (ref "RP3") (pin "2") (pinfunction "2_2") (pintype "passive"))
      (node (ref "RQ3") (pin "2") (pinfunction "2_2") (pintype "passive"))
    )
    (net (code "81") (name "Net-(QP4-G)") (class "Default")
      (node (ref "QP4") (pin "1") (pinfunction "G_1") (pintype "passive"))
      (node (ref "RP4") (pin "2") (pinfunction "2_2") (pintype "passive"))
      (node (ref "RQ4") (pin "2") (pinfunction "2_2") (pintype "passive"))
    )
    (net (code "82") (name "Net-(QP5-G)") (class "Default")
      (node (ref "QP5") (pin "1") (pinfunction "G_1") (pintype "passive"))
      (node (ref "RP5") (pin "2") (pinfunction "2_2") (pintype "passive"))
      (node (ref "RQ5") (pin "2") (pinfunction "2_2") (pintype "passive"))
    )
    (net (code "83") (name "Net-(QP6-G)") (class "Default")
      (node (ref "QP6") (pin "1") (pinfunction "G_1") (pintype "passive"))
      (node (ref "RP6") (pin "2") (pinfunction "2_2") (pintype "passive"))
      (node (ref "RQ6") (pin "2") (pinfunction "2_2") (pintype "passive"))
    )
    (net (code "84") (name "Net-(QP7-G)") (class "Default")
      (node (ref "QP7") (pin "1") (pinfunction "G_1") (pintype "passive"))
      (node (ref "RP7") (pin "2") (pinfunction "2_2") (pintype "passive"))
      (node (ref "RQ7") (pin "2") (pinfunction "2_2") (pintype "passive"))
    )
    (net (code "85") (name "Net-(QP8-G)") (class "Default")
      (node (ref "QP8") (pin "1") (pinfunction "G_1") (pintype "passive"))
      (node (ref "RP8") (pin "2") (pinfunction "2_2") (pintype "passive"))
      (node (ref "RQ8") (pin "2") (pinfunction "2_2") (pintype "passive"))
    )
    (net (code "86") (name "Net-(QP9-G)") (class "Default")
      (node (ref "QP9") (pin "1") (pinfunction "G_1") (pintype "passive"))
      (node (ref "RP9") (pin "2") (pinfunction "2_2") (pintype "passive"))
      (node (ref "RQ9") (pin "2") (pinfunction "2_2") (pintype "passive"))
    )
    (net (code "87") (name "Net-(QPP-G)") (class "Default")
      (node (ref "QPP") (pin "1") (pinfunction "G_1") (pintype "passive"))
      (node (ref "RPP") (pin "2") (pinfunction "2_2") (pintype "passive"))
      (node (ref "RSP") (pin "1") (pinfunction "1_1") (pintype "passive"))
    )
    (net (code "88") (name "Net-(QPV-G)") (class "Default")
      (node (ref "QPV") (pin "1") (pinfunction "G_1") (pintype "passive"))
      (node (ref "RPV") (pin "2") (pinfunction "2_2") (pintype "passive"))
      (node (ref "RSV") (pin "1") (pinfunction "1_1") (pintype "passive"))
    )
    (net (code "89") (name "unconnected-(J1-Pad2)") (class "Default")
      (node (ref "J1") (pin "2") (pinfunction "2_2") (pintype "passive"))
    )
    (net (code "90") (name "unconnected-(JEXT-Pad5)") (class "Default")
      (node (ref "JEXT") (pin "5") (pinfunction "5_5") (pintype "passive"))
    )
    (net (code "91") (name "unconnected-(JEXT-Pad6)") (class "Default")
      (node (ref "JEXT") (pin "6") (pinfunction "6_6") (pintype "passive"))
    )
  )
)
